# V14.net
KiCad netlist of a schematic drawn in EAGLE
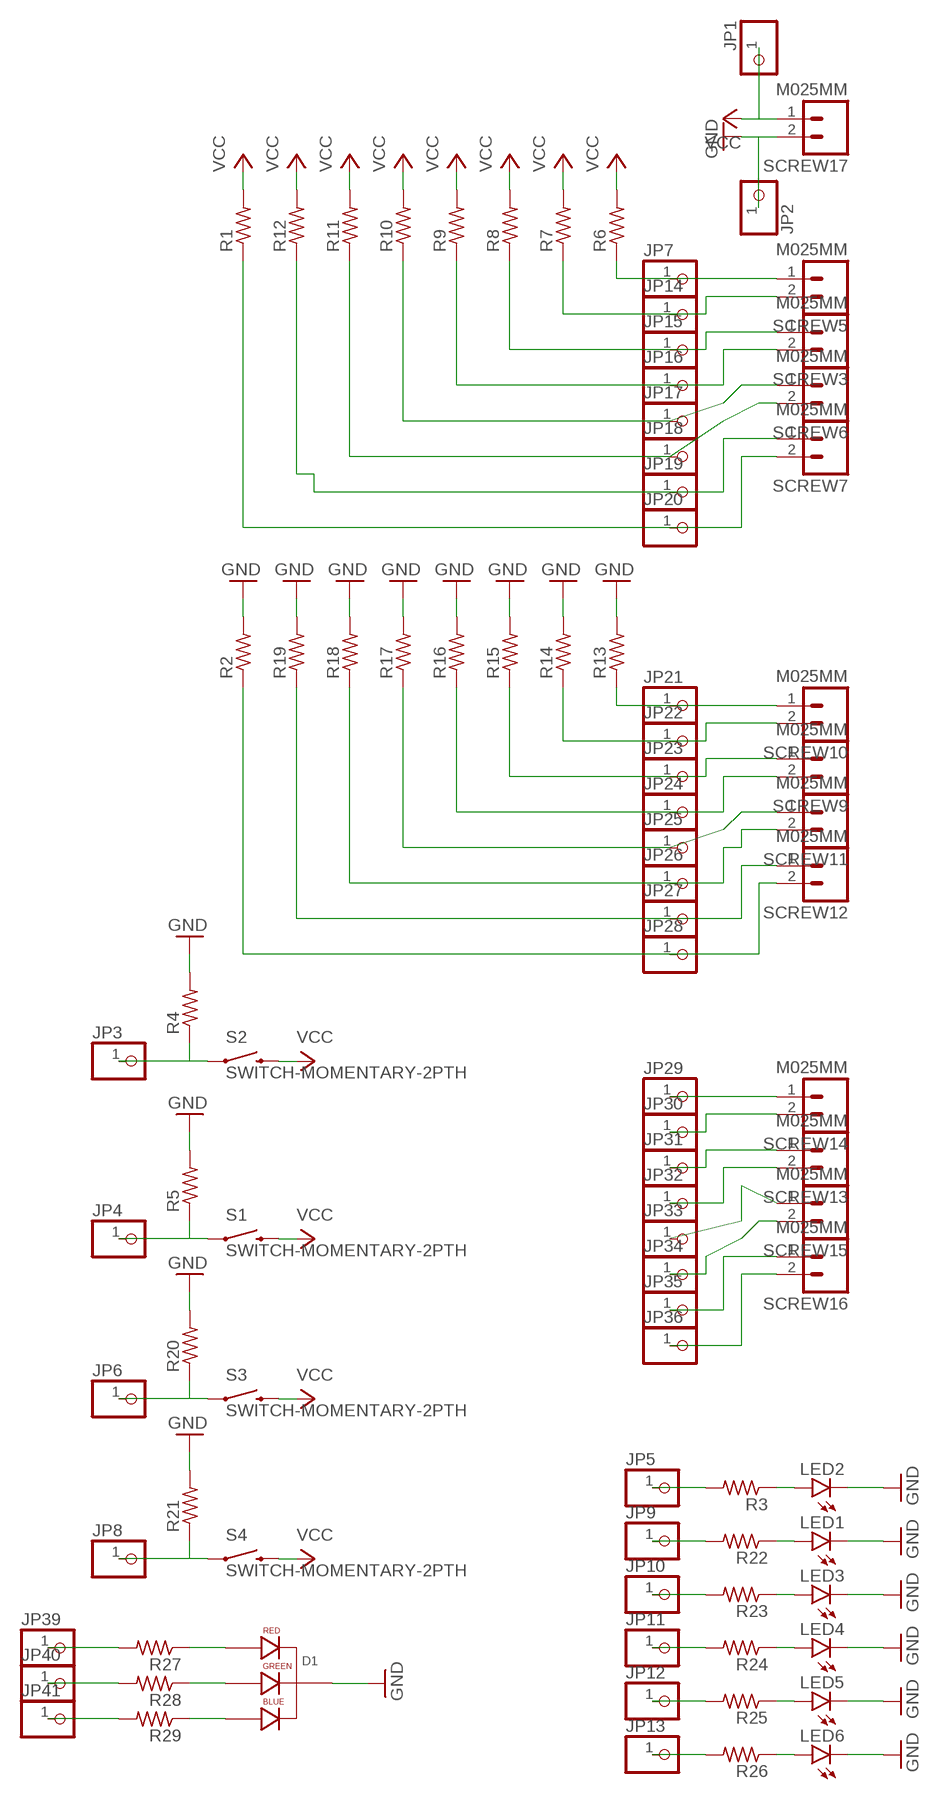
[diagram p0: schematic, sheet 1]

(export (version "E")
  (design (tool "Eeschema 10.0.6"))
  (components
    (comp (ref "D1")
      (value "LED-RGB-CC-THRUCLEAR")
      (footprint "eagle-import:LED-RGB-THRU")
      (libsource (lib "eagle-import") (part "LED-RGB-CC-THRUCLEAR"))
    )
    (comp (ref "JP1")
      (value "PINHD-1X1")
      (footprint "eagle-import:1X01")
      (libsource (lib "eagle-import") (part "PINHD-1X1"))
    )
    (comp (ref "JP2")
      (value "PINHD-1X1")
      (footprint "eagle-import:1X01")
      (libsource (lib "eagle-import") (part "PINHD-1X1"))
    )
    (comp (ref "JP3")
      (value "PINHD-1X1")
      (footprint "eagle-import:1X01")
      (libsource (lib "eagle-import") (part "PINHD-1X1"))
    )
    (comp (ref "JP4")
      (value "PINHD-1X1")
      (footprint "eagle-import:1X01")
      (libsource (lib "eagle-import") (part "PINHD-1X1"))
    )
    (comp (ref "JP5")
      (value "PINHD-1X1")
      (footprint "eagle-import:1X01")
      (libsource (lib "eagle-import") (part "PINHD-1X1"))
    )
    (comp (ref "JP6")
      (value "PINHD-1X1")
      (footprint "eagle-import:1X01")
      (libsource (lib "eagle-import") (part "PINHD-1X1"))
    )
    (comp (ref "JP7")
      (value "PINHD-1X1")
      (footprint "eagle-import:1X01")
      (libsource (lib "eagle-import") (part "PINHD-1X1"))
    )
    (comp (ref "JP8")
      (value "PINHD-1X1")
      (footprint "eagle-import:1X01")
      (libsource (lib "eagle-import") (part "PINHD-1X1"))
    )
    (comp (ref "JP9")
      (value "PINHD-1X1")
      (footprint "eagle-import:1X01")
      (libsource (lib "eagle-import") (part "PINHD-1X1"))
    )
    (comp (ref "JP10")
      (value "PINHD-1X1")
      (footprint "eagle-import:1X01")
      (libsource (lib "eagle-import") (part "PINHD-1X1"))
    )
    (comp (ref "JP11")
      (value "PINHD-1X1")
      (footprint "eagle-import:1X01")
      (libsource (lib "eagle-import") (part "PINHD-1X1"))
    )
    (comp (ref "JP12")
      (value "PINHD-1X1")
      (footprint "eagle-import:1X01")
      (libsource (lib "eagle-import") (part "PINHD-1X1"))
    )
    (comp (ref "JP13")
      (value "PINHD-1X1")
      (footprint "eagle-import:1X01")
      (libsource (lib "eagle-import") (part "PINHD-1X1"))
    )
    (comp (ref "JP14")
      (value "PINHD-1X1")
      (footprint "eagle-import:1X01")
      (libsource (lib "eagle-import") (part "PINHD-1X1"))
    )
    (comp (ref "JP15")
      (value "PINHD-1X1")
      (footprint "eagle-import:1X01")
      (libsource (lib "eagle-import") (part "PINHD-1X1"))
    )
    (comp (ref "JP16")
      (value "PINHD-1X1")
      (footprint "eagle-import:1X01")
      (libsource (lib "eagle-import") (part "PINHD-1X1"))
    )
    (comp (ref "JP17")
      (value "PINHD-1X1")
      (footprint "eagle-import:1X01")
      (libsource (lib "eagle-import") (part "PINHD-1X1"))
    )
    (comp (ref "JP18")
      (value "PINHD-1X1")
      (footprint "eagle-import:1X01")
      (libsource (lib "eagle-import") (part "PINHD-1X1"))
    )
    (comp (ref "JP19")
      (value "PINHD-1X1")
      (footprint "eagle-import:1X01")
      (libsource (lib "eagle-import") (part "PINHD-1X1"))
    )
    (comp (ref "JP20")
      (value "PINHD-1X1")
      (footprint "eagle-import:1X01")
      (libsource (lib "eagle-import") (part "PINHD-1X1"))
    )
    (comp (ref "JP21")
      (value "PINHD-1X1")
      (footprint "eagle-import:1X01")
      (libsource (lib "eagle-import") (part "PINHD-1X1"))
    )
    (comp (ref "JP22")
      (value "PINHD-1X1")
      (footprint "eagle-import:1X01")
      (libsource (lib "eagle-import") (part "PINHD-1X1"))
    )
    (comp (ref "JP23")
      (value "PINHD-1X1")
      (footprint "eagle-import:1X01")
      (libsource (lib "eagle-import") (part "PINHD-1X1"))
    )
    (comp (ref "JP24")
      (value "PINHD-1X1")
      (footprint "eagle-import:1X01")
      (libsource (lib "eagle-import") (part "PINHD-1X1"))
    )
    (comp (ref "JP25")
      (value "PINHD-1X1")
      (footprint "eagle-import:1X01")
      (libsource (lib "eagle-import") (part "PINHD-1X1"))
    )
    (comp (ref "JP26")
      (value "PINHD-1X1")
      (footprint "eagle-import:1X01")
      (libsource (lib "eagle-import") (part "PINHD-1X1"))
    )
    (comp (ref "JP27")
      (value "PINHD-1X1")
      (footprint "eagle-import:1X01")
      (libsource (lib "eagle-import") (part "PINHD-1X1"))
    )
    (comp (ref "JP28")
      (value "PINHD-1X1")
      (footprint "eagle-import:1X01")
      (libsource (lib "eagle-import") (part "PINHD-1X1"))
    )
    (comp (ref "JP29")
      (value "PINHD-1X1")
      (footprint "eagle-import:1X01")
      (libsource (lib "eagle-import") (part "PINHD-1X1"))
    )
    (comp (ref "JP30")
      (value "PINHD-1X1")
      (footprint "eagle-import:1X01")
      (libsource (lib "eagle-import") (part "PINHD-1X1"))
    )
    (comp (ref "JP31")
      (value "PINHD-1X1")
      (footprint "eagle-import:1X01")
      (libsource (lib "eagle-import") (part "PINHD-1X1"))
    )
    (comp (ref "JP32")
      (value "PINHD-1X1")
      (footprint "eagle-import:1X01")
      (libsource (lib "eagle-import") (part "PINHD-1X1"))
    )
    (comp (ref "JP33")
      (value "PINHD-1X1")
      (footprint "eagle-import:1X01")
      (libsource (lib "eagle-import") (part "PINHD-1X1"))
    )
    (comp (ref "JP34")
      (value "PINHD-1X1")
      (footprint "eagle-import:1X01")
      (libsource (lib "eagle-import") (part "PINHD-1X1"))
    )
    (comp (ref "JP35")
      (value "PINHD-1X1")
      (footprint "eagle-import:1X01")
      (libsource (lib "eagle-import") (part "PINHD-1X1"))
    )
    (comp (ref "JP36")
      (value "PINHD-1X1")
      (footprint "eagle-import:1X01")
      (libsource (lib "eagle-import") (part "PINHD-1X1"))
    )
    (comp (ref "JP39")
      (value "PINHD-1X1")
      (footprint "eagle-import:1X01")
      (libsource (lib "eagle-import") (part "PINHD-1X1"))
    )
    (comp (ref "JP40")
      (value "PINHD-1X1")
      (footprint "eagle-import:1X01")
      (libsource (lib "eagle-import") (part "PINHD-1X1"))
    )
    (comp (ref "JP41")
      (value "PINHD-1X1")
      (footprint "eagle-import:1X01")
      (libsource (lib "eagle-import") (part "PINHD-1X1"))
    )
    (comp (ref "LED1")
      (value "LED-3MM-NO_SILK")
      (footprint "eagle-import:LED3MM-NS")
      (libsource (lib "eagle-import") (part "LED-3MM-NO_SILK"))
    )
    (comp (ref "LED2")
      (value "LED-3MM-NO_SILK")
      (footprint "eagle-import:LED3MM-NS")
      (libsource (lib "eagle-import") (part "LED-3MM-NO_SILK"))
    )
    (comp (ref "LED3")
      (value "LED-3MM-NO_SILK")
      (footprint "eagle-import:LED3MM-NS")
      (libsource (lib "eagle-import") (part "LED-3MM-NO_SILK"))
    )
    (comp (ref "LED4")
      (value "LED-3MM-NO_SILK")
      (footprint "eagle-import:LED3MM-NS")
      (libsource (lib "eagle-import") (part "LED-3MM-NO_SILK"))
    )
    (comp (ref "LED5")
      (value "LED-3MM-NO_SILK")
      (footprint "eagle-import:LED3MM-NS")
      (libsource (lib "eagle-import") (part "LED-3MM-NO_SILK"))
    )
    (comp (ref "LED6")
      (value "LED-3MM-NO_SILK")
      (footprint "eagle-import:LED3MM-NS")
      (libsource (lib "eagle-import") (part "LED-3MM-NO_SILK"))
    )
    (comp (ref "R1")
      (value "R-US_0207/9")
      (footprint "eagle-import:0207_9")
      (libsource (lib "eagle-import") (part "R-US_0207/9"))
    )
    (comp (ref "R2")
      (value "R-US_0207/9")
      (footprint "eagle-import:0207_9")
      (libsource (lib "eagle-import") (part "R-US_0207/9"))
    )
    (comp (ref "R3")
      (value "R-US_0207/9")
      (footprint "eagle-import:0207_9")
      (libsource (lib "eagle-import") (part "R-US_0207/9"))
    )
    (comp (ref "R4")
      (value "R-US_0207/9")
      (footprint "eagle-import:0207_9")
      (libsource (lib "eagle-import") (part "R-US_0207/9"))
    )
    (comp (ref "R5")
      (value "R-US_0207/9")
      (footprint "eagle-import:0207_9")
      (libsource (lib "eagle-import") (part "R-US_0207/9"))
    )
    (comp (ref "R6")
      (value "R-US_0207/9")
      (footprint "eagle-import:0207_9")
      (libsource (lib "eagle-import") (part "R-US_0207/9"))
    )
    (comp (ref "R7")
      (value "R-US_0207/9")
      (footprint "eagle-import:0207_9")
      (libsource (lib "eagle-import") (part "R-US_0207/9"))
    )
    (comp (ref "R8")
      (value "R-US_0207/9")
      (footprint "eagle-import:0207_9")
      (libsource (lib "eagle-import") (part "R-US_0207/9"))
    )
    (comp (ref "R9")
      (value "R-US_0207/9")
      (footprint "eagle-import:0207_9")
      (libsource (lib "eagle-import") (part "R-US_0207/9"))
    )
    (comp (ref "R10")
      (value "R-US_0207/9")
      (footprint "eagle-import:0207_9")
      (libsource (lib "eagle-import") (part "R-US_0207/9"))
    )
    (comp (ref "R11")
      (value "R-US_0207/9")
      (footprint "eagle-import:0207_9")
      (libsource (lib "eagle-import") (part "R-US_0207/9"))
    )
    (comp (ref "R12")
      (value "R-US_0207/9")
      (footprint "eagle-import:0207_9")
      (libsource (lib "eagle-import") (part "R-US_0207/9"))
    )
    (comp (ref "R13")
      (value "R-US_0207/9")
      (footprint "eagle-import:0207_9")
      (libsource (lib "eagle-import") (part "R-US_0207/9"))
    )
    (comp (ref "R14")
      (value "R-US_0207/9")
      (footprint "eagle-import:0207_9")
      (libsource (lib "eagle-import") (part "R-US_0207/9"))
    )
    (comp (ref "R15")
      (value "R-US_0207/9")
      (footprint "eagle-import:0207_9")
      (libsource (lib "eagle-import") (part "R-US_0207/9"))
    )
    (comp (ref "R16")
      (value "R-US_0207/9")
      (footprint "eagle-import:0207_9")
      (libsource (lib "eagle-import") (part "R-US_0207/9"))
    )
    (comp (ref "R17")
      (value "R-US_0207/9")
      (footprint "eagle-import:0207_9")
      (libsource (lib "eagle-import") (part "R-US_0207/9"))
    )
    (comp (ref "R18")
      (value "R-US_0207/9")
      (footprint "eagle-import:0207_9")
      (libsource (lib "eagle-import") (part "R-US_0207/9"))
    )
    (comp (ref "R19")
      (value "R-US_0207/9")
      (footprint "eagle-import:0207_9")
      (libsource (lib "eagle-import") (part "R-US_0207/9"))
    )
    (comp (ref "R20")
      (value "R-US_0207/9")
      (footprint "eagle-import:0207_9")
      (libsource (lib "eagle-import") (part "R-US_0207/9"))
    )
    (comp (ref "R21")
      (value "R-US_0207/9")
      (footprint "eagle-import:0207_9")
      (libsource (lib "eagle-import") (part "R-US_0207/9"))
    )
    (comp (ref "R22")
      (value "R-US_0207/9")
      (footprint "eagle-import:0207_9")
      (libsource (lib "eagle-import") (part "R-US_0207/9"))
    )
    (comp (ref "R23")
      (value "R-US_0207/9")
      (footprint "eagle-import:0207_9")
      (libsource (lib "eagle-import") (part "R-US_0207/9"))
    )
    (comp (ref "R24")
      (value "R-US_0207/9")
      (footprint "eagle-import:0207_9")
      (libsource (lib "eagle-import") (part "R-US_0207/9"))
    )
    (comp (ref "R25")
      (value "R-US_0207/9")
      (footprint "eagle-import:0207_9")
      (libsource (lib "eagle-import") (part "R-US_0207/9"))
    )
    (comp (ref "R26")
      (value "R-US_0207/9")
      (footprint "eagle-import:0207_9")
      (libsource (lib "eagle-import") (part "R-US_0207/9"))
    )
    (comp (ref "R27")
      (value "R-US_0207/9")
      (footprint "eagle-import:0207_9")
      (libsource (lib "eagle-import") (part "R-US_0207/9"))
    )
    (comp (ref "R28")
      (value "R-US_0207/9")
      (footprint "eagle-import:0207_9")
      (libsource (lib "eagle-import") (part "R-US_0207/9"))
    )
    (comp (ref "R29")
      (value "R-US_0207/9")
      (footprint "eagle-import:0207_9")
      (libsource (lib "eagle-import") (part "R-US_0207/9"))
    )
    (comp (ref "S1")
      (value "SWITCH-MOMENTARY-2PTH")
      (footprint "eagle-import:TACTILE-PTH")
      (libsource (lib "eagle-import") (part "SWITCH-MOMENTARY-2PTH"))
    )
    (comp (ref "S2")
      (value "SWITCH-MOMENTARY-2PTH")
      (footprint "eagle-import:TACTILE-PTH")
      (libsource (lib "eagle-import") (part "SWITCH-MOMENTARY-2PTH"))
    )
    (comp (ref "S3")
      (value "SWITCH-MOMENTARY-2PTH")
      (footprint "eagle-import:TACTILE-PTH")
      (libsource (lib "eagle-import") (part "SWITCH-MOMENTARY-2PTH"))
    )
    (comp (ref "S4")
      (value "SWITCH-MOMENTARY-2PTH")
      (footprint "eagle-import:TACTILE-PTH")
      (libsource (lib "eagle-import") (part "SWITCH-MOMENTARY-2PTH"))
    )
    (comp (ref "SCREW3")
      (value "M025MM")
      (footprint "eagle-import:SCREWTERMINAL-5MM-2")
      (libsource (lib "eagle-import") (part "M025MM"))
    )
    (comp (ref "SCREW5")
      (value "M025MM")
      (footprint "eagle-import:SCREWTERMINAL-5MM-2")
      (libsource (lib "eagle-import") (part "M025MM"))
    )
    (comp (ref "SCREW6")
      (value "M025MM")
      (footprint "eagle-import:SCREWTERMINAL-5MM-2")
      (libsource (lib "eagle-import") (part "M025MM"))
    )
    (comp (ref "SCREW7")
      (value "M025MM")
      (footprint "eagle-import:SCREWTERMINAL-5MM-2")
      (libsource (lib "eagle-import") (part "M025MM"))
    )
    (comp (ref "SCREW9")
      (value "M025MM")
      (footprint "eagle-import:SCREWTERMINAL-5MM-2")
      (libsource (lib "eagle-import") (part "M025MM"))
    )
    (comp (ref "SCREW10")
      (value "M025MM")
      (footprint "eagle-import:SCREWTERMINAL-5MM-2")
      (libsource (lib "eagle-import") (part "M025MM"))
    )
    (comp (ref "SCREW11")
      (value "M025MM")
      (footprint "eagle-import:SCREWTERMINAL-5MM-2")
      (libsource (lib "eagle-import") (part "M025MM"))
    )
    (comp (ref "SCREW12")
      (value "M025MM")
      (footprint "eagle-import:SCREWTERMINAL-5MM-2")
      (libsource (lib "eagle-import") (part "M025MM"))
    )
    (comp (ref "SCREW13")
      (value "M025MM")
      (footprint "eagle-import:SCREWTERMINAL-5MM-2")
      (libsource (lib "eagle-import") (part "M025MM"))
    )
    (comp (ref "SCREW14")
      (value "M025MM")
      (footprint "eagle-import:SCREWTERMINAL-5MM-2")
      (libsource (lib "eagle-import") (part "M025MM"))
    )
    (comp (ref "SCREW15")
      (value "M025MM")
      (footprint "eagle-import:SCREWTERMINAL-5MM-2")
      (libsource (lib "eagle-import") (part "M025MM"))
    )
    (comp (ref "SCREW16")
      (value "M025MM")
      (footprint "eagle-import:SCREWTERMINAL-5MM-2")
      (libsource (lib "eagle-import") (part "M025MM"))
    )
    (comp (ref "SCREW17")
      (value "M025MM")
      (footprint "eagle-import:SCREWTERMINAL-5MM-2")
      (libsource (lib "eagle-import") (part "M025MM"))
    )
  )
  (nets
    (net (code "1") (name "GND") (class "Default")
      (node (ref "D1") (pin "2") (pinfunction "CATHODE_2") (pintype "bidirectional"))
      (node (ref "JP2") (pin "1") (pinfunction "1_1") (pintype "passive"))
      (node (ref "LED1") (pin "K") (pinfunction "C_K") (pintype "passive"))
      (node (ref "LED2") (pin "K") (pinfunction "C_K") (pintype "passive"))
      (node (ref "LED3") (pin "K") (pinfunction "C_K") (pintype "passive"))
      (node (ref "LED4") (pin "K") (pinfunction "C_K") (pintype "passive"))
      (node (ref "LED5") (pin "K") (pinfunction "C_K") (pintype "passive"))
      (node (ref "LED6") (pin "K") (pinfunction "C_K") (pintype "passive"))
      (node (ref "R13") (pin "2") (pinfunction "2_2") (pintype "passive"))
      (node (ref "R14") (pin "2") (pinfunction "2_2") (pintype "passive"))
      (node (ref "R15") (pin "2") (pinfunction "2_2") (pintype "passive"))
      (node (ref "R16") (pin "2") (pinfunction "2_2") (pintype "passive"))
      (node (ref "R17") (pin "2") (pinfunction "2_2") (pintype "passive"))
      (node (ref "R18") (pin "2") (pinfunction "2_2") (pintype "passive"))
      (node (ref "R19") (pin "2") (pinfunction "2_2") (pintype "passive"))
      (node (ref "R2") (pin "2") (pinfunction "2_2") (pintype "passive"))
      (node (ref "R20") (pin "2") (pinfunction "2_2") (pintype "passive"))
      (node (ref "R21") (pin "2") (pinfunction "2_2") (pintype "passive"))
      (node (ref "R4") (pin "2") (pinfunction "2_2") (pintype "passive"))
      (node (ref "R5") (pin "2") (pinfunction "2_2") (pintype "passive"))
      (node (ref "SCREW17") (pin "2") (pinfunction "2_2") (pintype "passive"))
    )
    (net (code "2") (name "Net-(D1-BLUE_CATHODE)") (class "Default")
      (node (ref "D1") (pin "4") (pinfunction "BLUE_CATHODE_4") (pintype "bidirectional"))
      (node (ref "R29") (pin "1") (pinfunction "1_1") (pintype "passive"))
    )
    (net (code "3") (name "Net-(D1-GREEN_CATHODE)") (class "Default")
      (node (ref "D1") (pin "3") (pinfunction "GREEN_CATHODE_3") (pintype "bidirectional"))
      (node (ref "R28") (pin "1") (pinfunction "1_1") (pintype "passive"))
    )
    (net (code "4") (name "Net-(D1-RED_CATHODE)") (class "Default")
      (node (ref "D1") (pin "1") (pinfunction "RED_CATHODE_1") (pintype "bidirectional"))
      (node (ref "R27") (pin "1") (pinfunction "1_1") (pintype "passive"))
    )
    (net (code "5") (name "Net-(JP3-Pad1)") (class "Default")
      (node (ref "JP3") (pin "1") (pinfunction "1_1") (pintype "passive"))
      (node (ref "R4") (pin "1") (pinfunction "1_1") (pintype "passive"))
      (node (ref "S2") (pin "1") (pinfunction "1_1") (pintype "passive"))
    )
    (net (code "6") (name "Net-(JP4-Pad1)") (class "Default")
      (node (ref "JP4") (pin "1") (pinfunction "1_1") (pintype "passive"))
      (node (ref "R5") (pin "1") (pinfunction "1_1") (pintype "passive"))
      (node (ref "S1") (pin "1") (pinfunction "1_1") (pintype "passive"))
    )
    (net (code "7") (name "Net-(JP5-Pad1)") (class "Default")
      (node (ref "JP5") (pin "1") (pinfunction "1_1") (pintype "passive"))
      (node (ref "R3") (pin "2") (pinfunction "2_2") (pintype "passive"))
    )
    (net (code "8") (name "Net-(JP6-Pad1)") (class "Default")
      (node (ref "JP6") (pin "1") (pinfunction "1_1") (pintype "passive"))
      (node (ref "R20") (pin "1") (pinfunction "1_1") (pintype "passive"))
      (node (ref "S3") (pin "1") (pinfunction "1_1") (pintype "passive"))
    )
    (net (code "9") (name "Net-(JP7-Pad1)") (class "Default")
      (node (ref "JP7") (pin "1") (pinfunction "1_1") (pintype "passive"))
      (node (ref "R6") (pin "1") (pinfunction "1_1") (pintype "passive"))
      (node (ref "SCREW5") (pin "1") (pinfunction "1_1") (pintype "passive"))
    )
    (net (code "10") (name "Net-(JP8-Pad1)") (class "Default")
      (node (ref "JP8") (pin "1") (pinfunction "1_1") (pintype "passive"))
      (node (ref "R21") (pin "1") (pinfunction "1_1") (pintype "passive"))
      (node (ref "S4") (pin "1") (pinfunction "1_1") (pintype "passive"))
    )
    (net (code "11") (name "Net-(JP9-Pad1)") (class "Default")
      (node (ref "JP9") (pin "1") (pinfunction "1_1") (pintype "passive"))
      (node (ref "R22") (pin "2") (pinfunction "2_2") (pintype "passive"))
    )
    (net (code "12") (name "Net-(JP10-Pad1)") (class "Default")
      (node (ref "JP10") (pin "1") (pinfunction "1_1") (pintype "passive"))
      (node (ref "R23") (pin "2") (pinfunction "2_2") (pintype "passive"))
    )
    (net (code "13") (name "Net-(JP11-Pad1)") (class "Default")
      (node (ref "JP11") (pin "1") (pinfunction "1_1") (pintype "passive"))
      (node (ref "R24") (pin "2") (pinfunction "2_2") (pintype "passive"))
    )
    (net (code "14") (name "Net-(JP12-Pad1)") (class "Default")
      (node (ref "JP12") (pin "1") (pinfunction "1_1") (pintype "passive"))
      (node (ref "R25") (pin "2") (pinfunction "2_2") (pintype "passive"))
    )
    (net (code "15") (name "Net-(JP13-Pad1)") (class "Default")
      (node (ref "JP13") (pin "1") (pinfunction "1_1") (pintype "passive"))
      (node (ref "R26") (pin "2") (pinfunction "2_2") (pintype "passive"))
    )
    (net (code "16") (name "Net-(JP14-Pad1)") (class "Default")
      (node (ref "JP14") (pin "1") (pinfunction "1_1") (pintype "passive"))
      (node (ref "R7") (pin "1") (pinfunction "1_1") (pintype "passive"))
      (node (ref "SCREW5") (pin "2") (pinfunction "2_2") (pintype "passive"))
    )
    (net (code "17") (name "Net-(JP15-Pad1)") (class "Default")
      (node (ref "JP15") (pin "1") (pinfunction "1_1") (pintype "passive"))
      (node (ref "R8") (pin "1") (pinfunction "1_1") (pintype "passive"))
      (node (ref "SCREW3") (pin "1") (pinfunction "1_1") (pintype "passive"))
    )
    (net (code "18") (name "Net-(JP16-Pad1)") (class "Default")
      (node (ref "JP16") (pin "1") (pinfunction "1_1") (pintype "passive"))
      (node (ref "R9") (pin "1") (pinfunction "1_1") (pintype "passive"))
      (node (ref "SCREW3") (pin "2") (pinfunction "2_2") (pintype "passive"))
    )
    (net (code "19") (name "Net-(JP17-Pad1)") (class "Default")
      (node (ref "JP17") (pin "1") (pinfunction "1_1") (pintype "passive"))
      (node (ref "R10") (pin "1") (pinfunction "1_1") (pintype "passive"))
      (node (ref "SCREW6") (pin "1") (pinfunction "1_1") (pintype "passive"))
    )
    (net (code "20") (name "Net-(JP18-Pad1)") (class "Default")
      (node (ref "JP18") (pin "1") (pinfunction "1_1") (pintype "passive"))
      (node (ref "R11") (pin "1") (pinfunction "1_1") (pintype "passive"))
      (node (ref "SCREW6") (pin "2") (pinfunction "2_2") (pintype "passive"))
    )
    (net (code "21") (name "Net-(JP19-Pad1)") (class "Default")
      (node (ref "JP19") (pin "1") (pinfunction "1_1") (pintype "passive"))
      (node (ref "R12") (pin "1") (pinfunction "1_1") (pintype "passive"))
      (node (ref "SCREW7") (pin "1") (pinfunction "1_1") (pintype "passive"))
    )
    (net (code "22") (name "Net-(JP20-Pad1)") (class "Default")
      (node (ref "JP20") (pin "1") (pinfunction "1_1") (pintype "passive"))
      (node (ref "R1") (pin "1") (pinfunction "1_1") (pintype "passive"))
      (node (ref "SCREW7") (pin "2") (pinfunction "2_2") (pintype "passive"))
    )
    (net (code "23") (name "Net-(JP21-Pad1)") (class "Default")
      (node (ref "JP21") (pin "1") (pinfunction "1_1") (pintype "passive"))
      (node (ref "R13") (pin "1") (pinfunction "1_1") (pintype "passive"))
      (node (ref "SCREW10") (pin "1") (pinfunction "1_1") (pintype "passive"))
    )
    (net (code "24") (name "Net-(JP22-Pad1)") (class "Default")
      (node (ref "JP22") (pin "1") (pinfunction "1_1") (pintype "passive"))
      (node (ref "R14") (pin "1") (pinfunction "1_1") (pintype "passive"))
      (node (ref "SCREW10") (pin "2") (pinfunction "2_2") (pintype "passive"))
    )
    (net (code "25") (name "Net-(JP23-Pad1)") (class "Default")
      (node (ref "JP23") (pin "1") (pinfunction "1_1") (pintype "passive"))
      (node (ref "R15") (pin "1") (pinfunction "1_1") (pintype "passive"))
      (node (ref "SCREW9") (pin "1") (pinfunction "1_1") (pintype "passive"))
    )
    (net (code "26") (name "Net-(JP24-Pad1)") (class "Default")
      (node (ref "JP24") (pin "1") (pinfunction "1_1") (pintype "passive"))
      (node (ref "R16") (pin "1") (pinfunction "1_1") (pintype "passive"))
      (node (ref "SCREW9") (pin "2") (pinfunction "2_2") (pintype "passive"))
    )
    (net (code "27") (name "Net-(JP25-Pad1)") (class "Default")
      (node (ref "JP25") (pin "1") (pinfunction "1_1") (pintype "passive"))
      (node (ref "R17") (pin "1") (pinfunction "1_1") (pintype "passive"))
      (node (ref "SCREW11") (pin "1") (pinfunction "1_1") (pintype "passive"))
    )
    (net (code "28") (name "Net-(JP26-Pad1)") (class "Default")
      (node (ref "JP26") (pin "1") (pinfunction "1_1") (pintype "passive"))
      (node (ref "R18") (pin "1") (pinfunction "1_1") (pintype "passive"))
      (node (ref "SCREW11") (pin "2") (pinfunction "2_2") (pintype "passive"))
    )
    (net (code "29") (name "Net-(JP27-Pad1)") (class "Default")
      (node (ref "JP27") (pin "1") (pinfunction "1_1") (pintype "passive"))
      (node (ref "R19") (pin "1") (pinfunction "1_1") (pintype "passive"))
      (node (ref "SCREW12") (pin "1") (pinfunction "1_1") (pintype "passive"))
    )
    (net (code "30") (name "Net-(JP28-Pad1)") (class "Default")
      (node (ref "JP28") (pin "1") (pinfunction "1_1") (pintype "passive"))
      (node (ref "R2") (pin "1") (pinfunction "1_1") (pintype "passive"))
      (node (ref "SCREW12") (pin "2") (pinfunction "2_2") (pintype "passive"))
    )
    (net (code "31") (name "Net-(JP29-Pad1)") (class "Default")
      (node (ref "JP29") (pin "1") (pinfunction "1_1") (pintype "passive"))
      (node (ref "SCREW14") (pin "1") (pinfunction "1_1") (pintype "passive"))
    )
    (net (code "32") (name "Net-(JP30-Pad1)") (class "Default")
      (node (ref "JP30") (pin "1") (pinfunction "1_1") (pintype "passive"))
      (node (ref "SCREW14") (pin "2") (pinfunction "2_2") (pintype "passive"))
    )
    (net (code "33") (name "Net-(JP31-Pad1)") (class "Default")
      (node (ref "JP31") (pin "1") (pinfunction "1_1") (pintype "passive"))
      (node (ref "SCREW13") (pin "1") (pinfunction "1_1") (pintype "passive"))
    )
    (net (code "34") (name "Net-(JP32-Pad1)") (class "Default")
      (node (ref "JP32") (pin "1") (pinfunction "1_1") (pintype "passive"))
      (node (ref "SCREW13") (pin "2") (pinfunction "2_2") (pintype "passive"))
    )
    (net (code "35") (name "Net-(JP33-Pad1)") (class "Default")
      (node (ref "JP33") (pin "1") (pinfunction "1_1") (pintype "passive"))
      (node (ref "SCREW15") (pin "1") (pinfunction "1_1") (pintype "passive"))
    )
    (net (code "36") (name "Net-(JP34-Pad1)") (class "Default")
      (node (ref "JP34") (pin "1") (pinfunction "1_1") (pintype "passive"))
      (node (ref "SCREW15") (pin "2") (pinfunction "2_2") (pintype "passive"))
    )
    (net (code "37") (name "Net-(JP35-Pad1)") (class "Default")
      (node (ref "JP35") (pin "1") (pinfunction "1_1") (pintype "passive"))
      (node (ref "SCREW16") (pin "1") (pinfunction "1_1") (pintype "passive"))
    )
    (net (code "38") (name "Net-(JP36-Pad1)") (class "Default")
      (node (ref "JP36") (pin "1") (pinfunction "1_1") (pintype "passive"))
      (node (ref "SCREW16") (pin "2") (pinfunction "2_2") (pintype "passive"))
    )
    (net (code "39") (name "Net-(JP39-Pad1)") (class "Default")
      (node (ref "JP39") (pin "1") (pinfunction "1_1") (pintype "passive"))
      (node (ref "R27") (pin "2") (pinfunction "2_2") (pintype "passive"))
    )
    (net (code "40") (name "Net-(JP40-Pad1)") (class "Default")
      (node (ref "JP40") (pin "1") (pinfunction "1_1") (pintype "passive"))
      (node (ref "R28") (pin "2") (pinfunction "2_2") (pintype "passive"))
    )
    (net (code "41") (name "Net-(JP41-Pad1)") (class "Default")
      (node (ref "JP41") (pin "1") (pinfunction "1_1") (pintype "passive"))
      (node (ref "R29") (pin "2") (pinfunction "2_2") (pintype "passive"))
    )
    (net (code "42") (name "Net-(LED1-PadA)") (class "Default")
      (node (ref "LED1") (pin "A") (pinfunction "A_A") (pintype "passive"))
      (node (ref "R22") (pin "1") (pinfunction "1_1") (pintype "passive"))
    )
    (net (code "43") (name "Net-(LED2-PadA)") (class "Default")
      (node (ref "LED2") (pin "A") (pinfunction "A_A") (pintype "passive"))
      (node (ref "R3") (pin "1") (pinfunction "1_1") (pintype "passive"))
    )
    (net (code "44") (name "Net-(LED3-PadA)") (class "Default")
      (node (ref "LED3") (pin "A") (pinfunction "A_A") (pintype "passive"))
      (node (ref "R23") (pin "1") (pinfunction "1_1") (pintype "passive"))
    )
    (net (code "45") (name "Net-(LED4-PadA)") (class "Default")
      (node (ref "LED4") (pin "A") (pinfunction "A_A") (pintype "passive"))
      (node (ref "R24") (pin "1") (pinfunction "1_1") (pintype "passive"))
    )
    (net (code "46") (name "Net-(LED5-PadA)") (class "Default")
      (node (ref "LED5") (pin "A") (pinfunction "A_A") (pintype "passive"))
      (node (ref "R25") (pin "1") (pinfunction "1_1") (pintype "passive"))
    )
    (net (code "47") (name "Net-(LED6-PadA)") (class "Default")
      (node (ref "LED6") (pin "A") (pinfunction "A_A") (pintype "passive"))
      (node (ref "R26") (pin "1") (pinfunction "1_1") (pintype "passive"))
    )
    (net (code "48") (name "VCC") (class "Default")
      (node (ref "JP1") (pin "1") (pinfunction "1_1") (pintype "passive"))
      (node (ref "R1") (pin "2") (pinfunction "2_2") (pintype "passive"))
      (node (ref "R10") (pin "2") (pinfunction "2_2") (pintype "passive"))
      (node (ref "R11") (pin "2") (pinfunction "2_2") (pintype "passive"))
      (node (ref "R12") (pin "2") (pinfunction "2_2") (pintype "passive"))
      (node (ref "R6") (pin "2") (pinfunction "2_2") (pintype "passive"))
      (node (ref "R7") (pin "2") (pinfunction "2_2") (pintype "passive"))
      (node (ref "R8") (pin "2") (pinfunction "2_2") (pintype "passive"))
      (node (ref "R9") (pin "2") (pinfunction "2_2") (pintype "passive"))
      (node (ref "S1") (pin "3") (pinfunction "2_3") (pintype "passive"))
      (node (ref "S2") (pin "3") (pinfunction "2_3") (pintype "passive"))
      (node (ref "S3") (pin "3") (pinfunction "2_3") (pintype "passive"))
      (node (ref "S4") (pin "3") (pinfunction "2_3") (pintype "passive"))
      (node (ref "SCREW17") (pin "1") (pinfunction "1_1") (pintype "passive"))
    )
  )
)
